# DRVPowerOutputs.net
KiCad netlist of a schematic drawn in Altium Designer
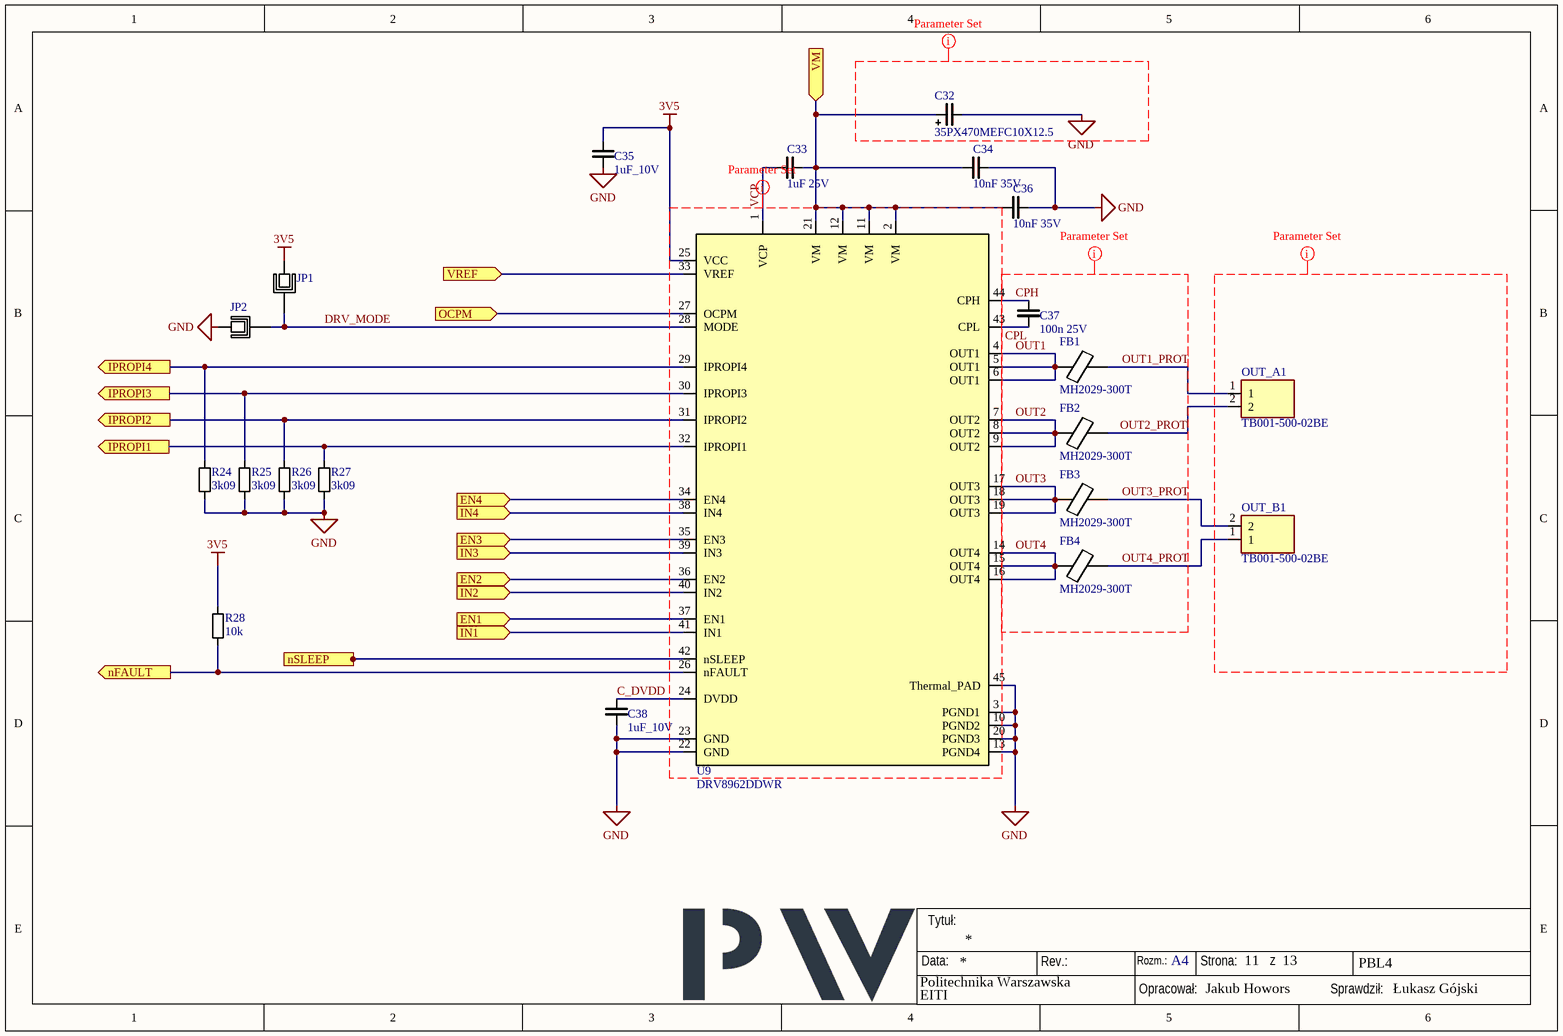
[diagram p0: DRVPowerOutputs.SchDoc]

(export (version "E")
  (design (tool "Eeschema 10.0.6"))
  (components
    (comp (ref "C32")
      (value "35PX470MEFC10X12.5")
      (footprint "CAP_PKPZ_10X12P5_LOW_RUB")
      (description "470 µF 35 V Aluminum Electrolytic Capacitors Radial, Can 2000 Hrs @ 105°C")
      (fields (field (name "VOLTAGE") "35V") (field (name "TOLERANCE") "20%"))
      (libsource (lib "Common") (part "C_Pol_470uF_35V"))
    )
    (comp (ref "C33")
      (value "1uF 25V")
      (footprint "C_0603")
      (description "Ceramic capacitor")
      (fields (field (name "VOLTAGE") "25V") (field (name "TOLERANCE") "10%"))
      (libsource (lib "Common") (part "C_1uF_25V"))
    )
    (comp (ref "C34")
      (value "10nF 35V")
      (footprint "0603_CAP")
      (description "Ceramic capacitor")
      (fields (field (name "VOLTAGE") "35V") (field (name "TOLERANCE") "5%"))
      (libsource (lib "IOLib") (part "Cap_10nF"))
    )
    (comp (ref "C35")
      (value "1uF_10V")
      (footprint "C_0603")
      (description "Ceramic capacitor")
      (fields (field (name "VOLTAGE") "10V") (field (name "TOLERANCE") "10%"))
      (libsource (lib "Common") (part "C_1uF_10V"))
    )
    (comp (ref "C36")
      (value "10nF 35V")
      (footprint "0603_CAP")
      (description "Ceramic capacitor")
      (fields (field (name "VOLTAGE") "35V") (field (name "TOLERANCE") "5%"))
      (libsource (lib "IOLib") (part "Cap_10nF"))
    )
    (comp (ref "C37")
      (value "100n 25V")
      (footprint "C_0603")
      (description "Ceramic capacitor")
      (fields (field (name "VOLTAGE") "25V") (field (name "TOLERANCE") "10%"))
      (libsource (lib "Common") (part "C_100nF_25V"))
    )
    (comp (ref "C38")
      (value "1uF_10V")
      (footprint "C_0603")
      (description "Ceramic capacitor")
      (fields (field (name "VOLTAGE") "10V") (field (name "TOLERANCE") "10%"))
      (libsource (lib "Common") (part "C_1uF_10V"))
    )
    (comp (ref "FB1")
      (value "MH2029-300T")
      (footprint "MH2029-300T")
      (description "Ferrite bead")
      (fields (field (name "MANUFACTURER") "Bourns Inc."))
      (libsource (lib "IOLib") (part "FerriteBead_8A5"))
    )
    (comp (ref "FB2")
      (value "MH2029-300T")
      (footprint "MH2029-300T")
      (description "Ferrite bead")
      (fields (field (name "MANUFACTURER") "Bourns Inc."))
      (libsource (lib "IOLib") (part "FerriteBead_8A5"))
    )
    (comp (ref "FB3")
      (value "MH2029-300T")
      (footprint "MH2029-300T")
      (description "Ferrite bead")
      (fields (field (name "MANUFACTURER") "Bourns Inc."))
      (libsource (lib "IOLib") (part "FerriteBead_8A5"))
    )
    (comp (ref "FB4")
      (value "MH2029-300T")
      (footprint "MH2029-300T")
      (description "Ferrite bead")
      (fields (field (name "MANUFACTURER") "Bourns Inc."))
      (libsource (lib "IOLib") (part "FerriteBead_8A5"))
    )
    (comp (ref "JP1")
      (value "JUMPER")
      (footprint "Jumper")
      (description "Jumper on traces")
      (libsource (lib "Common") (part "Jumper x2"))
    )
    (comp (ref "JP2")
      (value "JUMPER")
      (footprint "Jumper")
      (description "Jumper on traces")
      (libsource (lib "Common") (part "Jumper x2"))
    )
    (comp (ref "OUT_A1")
      (value "TB001-500-02BE")
      (footprint "TB00150002BE")
      (description "Screw terminal x2 5mm spacing")
      (fields (field (name "MANUFACTURER") "Same Sky"))
      (libsource (lib "") (part "Screw Terminal x2 5mm_1"))
    )
    (comp (ref "OUT_B1")
      (value "TB001-500-02BE")
      (footprint "TB00150002BE")
      (description "Screw terminal x2 5mm spacing")
      (fields (field (name "MANUFACTURER") "Same Sky"))
      (libsource (lib "Common") (part "Screw Terminal x2 5mm"))
    )
    (comp (ref "R24")
      (value "3k09")
      (footprint "R_0603")
      (description "Resistor")
      (fields (field (name "TOLERANCE") "1%") (field (name "POWER") "100mW"))
      (libsource (lib "Common") (part "R_3k09"))
    )
    (comp (ref "R25")
      (value "3k09")
      (footprint "R_0603")
      (description "Resistor")
      (fields (field (name "TOLERANCE") "1%") (field (name "POWER") "100mW"))
      (libsource (lib "Common") (part "R_3k09"))
    )
    (comp (ref "R26")
      (value "3k09")
      (footprint "R_0603")
      (description "Resistor")
      (fields (field (name "TOLERANCE") "1%") (field (name "POWER") "100mW"))
      (libsource (lib "Common") (part "R_3k09"))
    )
    (comp (ref "R27")
      (value "3k09")
      (footprint "R_0603")
      (description "Resistor")
      (fields (field (name "TOLERANCE") "1%") (field (name "POWER") "100mW"))
      (libsource (lib "Common") (part "R_3k09"))
    )
    (comp (ref "R28")
      (value "10k")
      (footprint "R_0603")
      (description "Resistor")
      (fields (field (name "TOLERANCE") "1%") (field (name "POWER") "100mW"))
      (libsource (lib "Common") (part "R_10k"))
    )
    (comp (ref "U9")
      (value "DRV8962DDWR")
      (footprint "DDW0044E-MFG")
      (description "65-V four-channel half-bridge driver with current sense outputs 44-HTSSOP")
      (fields (field (name "MANUFACTURER") "Texas Instruments"))
      (libsource (lib "IOLib") (part "IC_drv8962_PDRV8962DDWR"))
    )
  )
  (nets
    (net (code "1") (name "/CPH") (class "Default")
      (node (ref "C37") (pin "2") (pinfunction "2_2") (pintype "passive"))
      (node (ref "U9") (pin "44") (pinfunction "CPH_44") (pintype "passive"))
    )
    (net (code "2") (name "/CPL") (class "Default")
      (node (ref "C37") (pin "1") (pinfunction "1_1") (pintype "passive"))
      (node (ref "U9") (pin "43") (pinfunction "CPL_43") (pintype "passive"))
    )
    (net (code "3") (name "/C_DVDD") (class "Default")
      (node (ref "C38") (pin "2") (pinfunction "2_2") (pintype "passive"))
      (node (ref "U9") (pin "24") (pinfunction "DVDD_24") (pintype "passive"))
    )
    (net (code "4") (name "/DRV_MODE") (class "Default")
      (node (ref "JP1") (pin "2") (pinfunction "2_2") (pintype "passive"))
      (node (ref "JP2") (pin "2") (pinfunction "2_2") (pintype "passive"))
      (node (ref "U9") (pin "28") (pinfunction "MODE_28") (pintype "passive"))
    )
    (net (code "5") (name "/EN1") (class "Default")
      (node (ref "U9") (pin "37") (pinfunction "EN1_37") (pintype "passive"))
    )
    (net (code "6") (name "/EN2") (class "Default")
      (node (ref "U9") (pin "36") (pinfunction "EN2_36") (pintype "passive"))
    )
    (net (code "7") (name "/EN3") (class "Default")
      (node (ref "U9") (pin "35") (pinfunction "EN3_35") (pintype "passive"))
    )
    (net (code "8") (name "/EN4") (class "Default")
      (node (ref "U9") (pin "34") (pinfunction "EN4_34") (pintype "passive"))
    )
    (net (code "9") (name "/IN1") (class "Default")
      (node (ref "U9") (pin "41") (pinfunction "IN1_41") (pintype "passive"))
    )
    (net (code "10") (name "/IN2") (class "Default")
      (node (ref "U9") (pin "40") (pinfunction "IN2_40") (pintype "passive"))
    )
    (net (code "11") (name "/IN3") (class "Default")
      (node (ref "U9") (pin "39") (pinfunction "IN3_39") (pintype "passive"))
    )
    (net (code "12") (name "/IN4") (class "Default")
      (node (ref "U9") (pin "38") (pinfunction "IN4_38") (pintype "passive"))
    )
    (net (code "13") (name "/IPROPI1") (class "Default")
      (node (ref "R27") (pin "2") (pinfunction "2_2") (pintype "passive"))
      (node (ref "U9") (pin "32") (pinfunction "IPROPI1_32") (pintype "passive"))
    )
    (net (code "14") (name "/IPROPI2") (class "Default")
      (node (ref "R26") (pin "2") (pinfunction "2_2") (pintype "passive"))
      (node (ref "U9") (pin "31") (pinfunction "IPROPI2_31") (pintype "passive"))
    )
    (net (code "15") (name "/IPROPI3") (class "Default")
      (node (ref "R25") (pin "2") (pinfunction "2_2") (pintype "passive"))
      (node (ref "U9") (pin "30") (pinfunction "IPROPI3_30") (pintype "passive"))
    )
    (net (code "16") (name "/IPROPI4") (class "Default")
      (node (ref "R24") (pin "2") (pinfunction "2_2") (pintype "passive"))
      (node (ref "U9") (pin "29") (pinfunction "IPROPI4_29") (pintype "passive"))
    )
    (net (code "17") (name "/OCPM") (class "Default")
      (node (ref "U9") (pin "27") (pinfunction "OCPM_27") (pintype "passive"))
    )
    (net (code "18") (name "/OUT1") (class "Default")
      (node (ref "FB1") (pin "1") (pinfunction "1_1") (pintype "passive"))
      (node (ref "U9") (pin "4") (pinfunction "OUT1_4") (pintype "passive"))
      (node (ref "U9") (pin "5") (pinfunction "OUT1_5") (pintype "passive"))
      (node (ref "U9") (pin "6") (pinfunction "OUT1_6") (pintype "passive"))
    )
    (net (code "19") (name "/OUT1_PROT") (class "Default")
      (node (ref "FB1") (pin "2") (pinfunction "2_2") (pintype "passive"))
      (node (ref "OUT_A1") (pin "1") (pinfunction "1_1") (pintype "passive"))
    )
    (net (code "20") (name "/OUT2") (class "Default")
      (node (ref "FB2") (pin "1") (pinfunction "1_1") (pintype "passive"))
      (node (ref "U9") (pin "7") (pinfunction "OUT2_7") (pintype "passive"))
      (node (ref "U9") (pin "8") (pinfunction "OUT2_8") (pintype "passive"))
      (node (ref "U9") (pin "9") (pinfunction "OUT2_9") (pintype "passive"))
    )
    (net (code "21") (name "/OUT2_PROT") (class "Default")
      (node (ref "FB2") (pin "2") (pinfunction "2_2") (pintype "passive"))
      (node (ref "OUT_A1") (pin "2") (pinfunction "2_2") (pintype "passive"))
    )
    (net (code "22") (name "/OUT3") (class "Default")
      (node (ref "FB3") (pin "1") (pinfunction "1_1") (pintype "passive"))
      (node (ref "U9") (pin "17") (pinfunction "OUT3_17") (pintype "passive"))
      (node (ref "U9") (pin "18") (pinfunction "OUT3_18") (pintype "passive"))
      (node (ref "U9") (pin "19") (pinfunction "OUT3_19") (pintype "passive"))
    )
    (net (code "23") (name "/OUT3_PROT") (class "Default")
      (node (ref "FB3") (pin "2") (pinfunction "2_2") (pintype "passive"))
      (node (ref "OUT_B1") (pin "2") (pinfunction "2_2") (pintype "passive"))
    )
    (net (code "24") (name "/OUT4") (class "Default")
      (node (ref "FB4") (pin "1") (pinfunction "1_1") (pintype "passive"))
      (node (ref "U9") (pin "14") (pinfunction "OUT4_14") (pintype "passive"))
      (node (ref "U9") (pin "15") (pinfunction "OUT4_15") (pintype "passive"))
      (node (ref "U9") (pin "16") (pinfunction "OUT4_16") (pintype "passive"))
    )
    (net (code "25") (name "/OUT4_PROT") (class "Default")
      (node (ref "FB4") (pin "2") (pinfunction "2_2") (pintype "passive"))
      (node (ref "OUT_B1") (pin "1") (pinfunction "1_1") (pintype "passive"))
    )
    (net (code "26") (name "/VCP") (class "Default")
      (node (ref "C33") (pin "1") (pinfunction "1_1") (pintype "passive"))
      (node (ref "U9") (pin "1") (pinfunction "VCP_1") (pintype "passive"))
    )
    (net (code "27") (name "/VM") (class "Default")
      (node (ref "C32") (pin "1") (pinfunction "1_1") (pintype "passive"))
      (node (ref "C33") (pin "2") (pinfunction "2_2") (pintype "passive"))
      (node (ref "C34") (pin "1") (pinfunction "1_1") (pintype "passive"))
      (node (ref "C36") (pin "1") (pinfunction "1_1") (pintype "passive"))
      (node (ref "U9") (pin "11") (pinfunction "VM_11") (pintype "passive"))
      (node (ref "U9") (pin "12") (pinfunction "VM_12") (pintype "passive"))
      (node (ref "U9") (pin "2") (pinfunction "VM_2") (pintype "passive"))
      (node (ref "U9") (pin "21") (pinfunction "VM_21") (pintype "passive"))
    )
    (net (code "28") (name "/VREF") (class "Default")
      (node (ref "U9") (pin "33") (pinfunction "VREF_33") (pintype "passive"))
    )
    (net (code "29") (name "/nFAULT") (class "Default")
      (node (ref "R28") (pin "2") (pinfunction "2_2") (pintype "passive"))
      (node (ref "U9") (pin "26") (pinfunction "nFAULT_26") (pintype "passive"))
    )
    (net (code "30") (name "/nSLEEP") (class "Default")
      (node (ref "U9") (pin "42") (pinfunction "nSLEEP_42") (pintype "passive"))
    )
    (net (code "31") (name "3V5") (class "Default")
      (node (ref "C35") (pin "2") (pinfunction "2_2") (pintype "passive"))
      (node (ref "JP1") (pin "1") (pinfunction "1_1") (pintype "passive"))
      (node (ref "R28") (pin "1") (pinfunction "1_1") (pintype "passive"))
      (node (ref "U9") (pin "25") (pinfunction "VCC_25") (pintype "passive"))
    )
    (net (code "32") (name "GND") (class "Default")
      (node (ref "C32") (pin "2") (pinfunction "2_2") (pintype "passive"))
      (node (ref "C34") (pin "2") (pinfunction "2_2") (pintype "passive"))
      (node (ref "C35") (pin "1") (pinfunction "1_1") (pintype "passive"))
      (node (ref "C36") (pin "2") (pinfunction "2_2") (pintype "passive"))
      (node (ref "C38") (pin "1") (pinfunction "1_1") (pintype "passive"))
      (node (ref "JP2") (pin "1") (pinfunction "1_1") (pintype "passive"))
      (node (ref "R24") (pin "1") (pinfunction "1_1") (pintype "passive"))
      (node (ref "R25") (pin "1") (pinfunction "1_1") (pintype "passive"))
      (node (ref "R26") (pin "1") (pinfunction "1_1") (pintype "passive"))
      (node (ref "R27") (pin "1") (pinfunction "1_1") (pintype "passive"))
      (node (ref "U9") (pin "10") (pinfunction "PGND2_10") (pintype "passive"))
      (node (ref "U9") (pin "13") (pinfunction "PGND4_13") (pintype "passive"))
      (node (ref "U9") (pin "20") (pinfunction "PGND3_20") (pintype "passive"))
      (node (ref "U9") (pin "22") (pinfunction "GND_22") (pintype "passive"))
      (node (ref "U9") (pin "23") (pinfunction "GND_23") (pintype "passive"))
      (node (ref "U9") (pin "3") (pinfunction "PGND1_3") (pintype "passive"))
      (node (ref "U9") (pin "45") (pinfunction "Thermal_PAD_45") (pintype "passive"))
    )
  )
)
